# Sheet_SmartTerminal_2024-09-08.net
KiCad netlist of a schematic drawn in Altium Designer
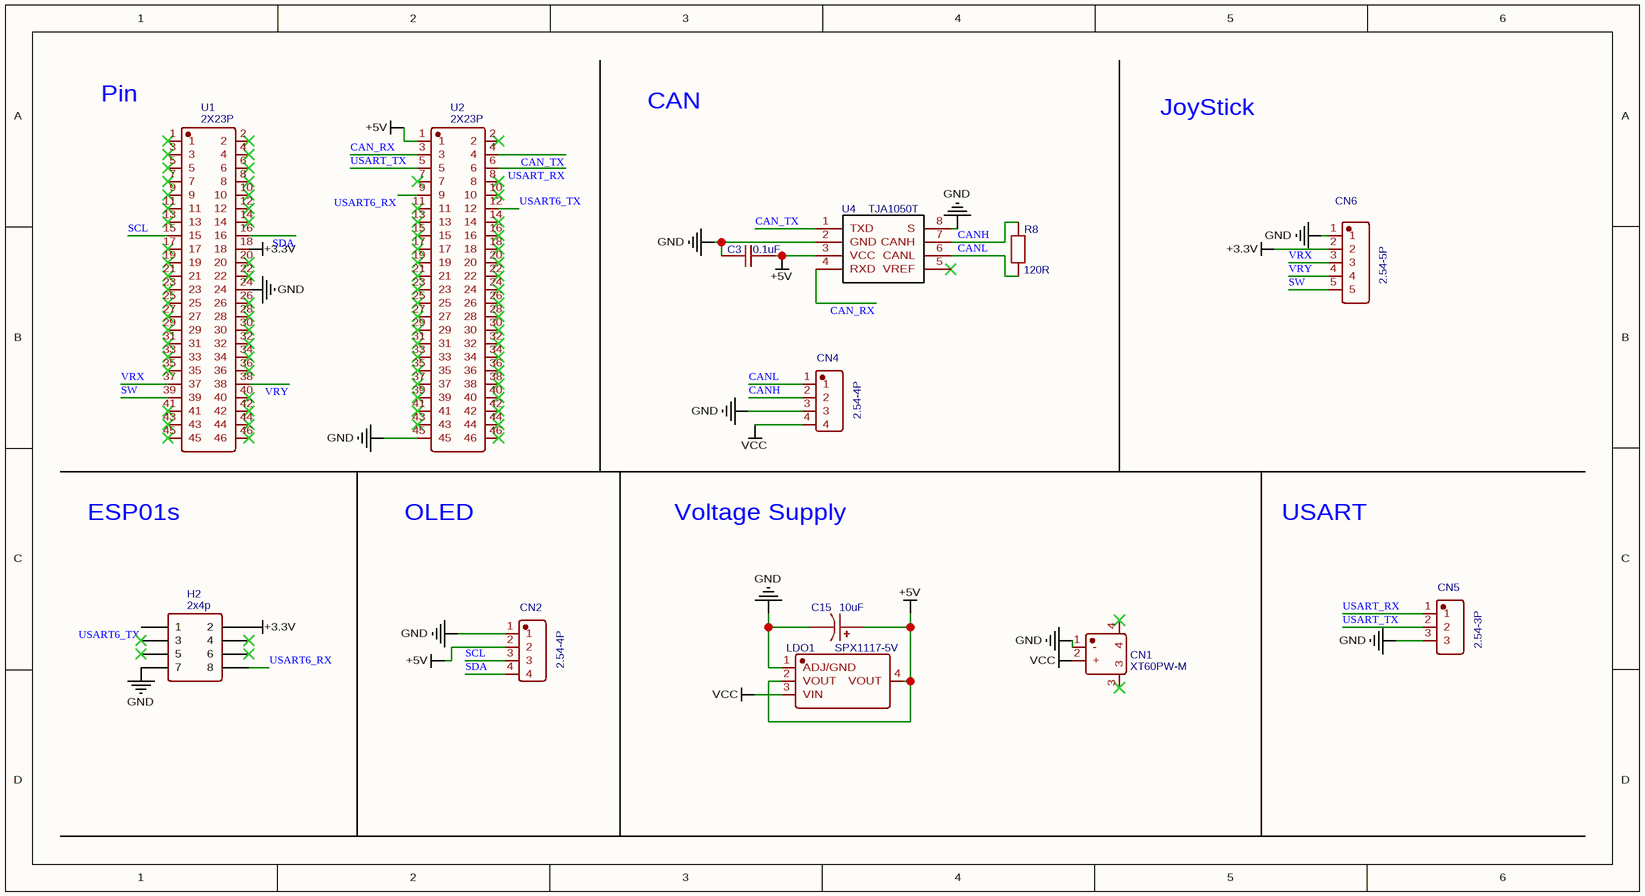
[diagram p0: Sheet_SmartTerminal_2024-09-08.schdoc]

(export (version "E")
  (design (tool "Eeschema 10.0.6"))
  (components
    (comp (ref "C3")
      (value "0.1uF")
      (fields (field (name "CONTRIBUTOR") "LCEDA_Lib"))
      (libsource (lib "altium-import") (part "root_0_0.1uF_"))
    )
    (comp (ref "C15")
      (value "10uF")
      (fields (field (name "CONTRIBUTOR") "LCEDA_Lib"))
      (libsource (lib "altium-import") (part "root_2_10uF_"))
    )
    (comp (ref "CN1")
      (value "XT60PW-M")
      (fields (field (name "MANUFACTURER") "AMASS(艾迈斯)") (field (name "CONTRIBUTOR") "LCSC"))
      (libsource (lib "altium-import") (part "root_0_XT60PW-M_"))
    )
    (comp (ref "CN2")
      (value "2.54-4P")
      (fields
        (field (name "MANUFACTURER") "HCTL(华灿天禄)")
        (field (name "MANUFACTURER PART") "XH-4AW")
        (field (name "CONTRIBUTOR") "LCSC")
      )
      (libsource (lib "altium-import") (part "root_0_2.54-4P_"))
    )
    (comp (ref "CN4")
      (value "2.54-4P")
      (fields
        (field (name "MANUFACTURER") "HCTL(华灿天禄)")
        (field (name "MANUFACTURER PART") "XH-4AW")
        (field (name "CONTRIBUTOR") "LCSC")
      )
      (libsource (lib "altium-import") (part "root_0_2.54-4P_"))
    )
    (comp (ref "CN5")
      (value "2.54-3P")
      (fields
        (field (name "MANUFACTURER") "HCTL(华灿天禄)")
        (field (name "MANUFACTURER PART") "XH-3AW")
        (field (name "CONTRIBUTOR") "LCSC")
      )
      (libsource (lib "altium-import") (part "root_0_2.54-3P_"))
    )
    (comp (ref "CN6")
      (value "2.54-5P")
      (fields
        (field (name "MANUFACTURER") "HCTL(华灿天禄)")
        (field (name "MANUFACTURER PART") "XH-5AW")
        (field (name "CONTRIBUTOR") "LCSC")
      )
      (libsource (lib "altium-import") (part "root_0_2.54-5P_"))
    )
    (comp (ref "H2")
      (value "2x4p")
      (fields
        (field (name "MANUFACTURER") "CONNFLY")
        (field (name "MANUFACTURER PART") "DS1023-2*4SF11")
        (field (name "CONTRIBUTOR") "LCSC")
      )
      (libsource (lib "altium-import") (part "root_0_2x4p_"))
    )
    (comp (ref "LDO1")
      (value "SPX1117-5V")
      (fields
        (field (name "BOM_MANUFACTURER PART") "SPX1117M3-L/TR")
        (field (name "BOM_SUPPLIER PART") "C67402")
      )
      (libsource (lib "altium-import") (part "root_0_SPX1117-5V_"))
    )
    (comp (ref "R8")
      (value "120R")
      (fields (field (name "CONTRIBUTOR") "LCEDA_Lib"))
      (libsource (lib "altium-import") (part "root_1_120R_"))
    )
    (comp (ref "U1")
      (value "2X23P")
      (fields
        (field (name "MANUFACTURER") "XKB Connection(中国星坤)")
        (field (name "MANUFACTURER PART") "X6522WV-2x23H-C60D30-E80")
        (field (name "CONTRIBUTOR") "lcsc")
      )
      (libsource (lib "altium-import") (part "root_0_2X23P_"))
    )
    (comp (ref "U2")
      (value "2X23P")
      (fields
        (field (name "MANUFACTURER") "XKB Connection(中国星坤)")
        (field (name "MANUFACTURER PART") "X6522WV-2x23H-C60D30-E80")
        (field (name "CONTRIBUTOR") "lcsc")
      )
      (libsource (lib "altium-import") (part "root_0_2X23P_"))
    )
    (comp (ref "U4")
      (value "TJA1050T")
      (fields
        (field (name "BOM_MANUFACTURER PART") "TJA1050T/CM,118")
        (field (name "BOM_SUPPLIER PART") "C6952")
      )
      (libsource (lib "altium-import") (part "root_0_TJA1050T_"))
    )
  )
  (nets
    (net (code "1") (name "+3.3V") (class "Default")
      (node (ref "CN6") (pin "2") (pinfunction "2_2") (pintype "passive"))
      (node (ref "H2") (pin "2") (pinfunction "2_2") (pintype "passive"))
      (node (ref "U1") (pin "18") (pinfunction "18_18") (pintype "passive"))
    )
    (net (code "2") (name "+5V") (class "Default")
      (node (ref "C15") (pin "1") (pinfunction "1_1") (pintype "passive"))
      (node (ref "C3") (pin "2") (pinfunction "2_2") (pintype "passive"))
      (node (ref "CN2") (pin "2") (pinfunction "2_2") (pintype "passive"))
      (node (ref "LDO1") (pin "2") (pinfunction "VOUT_2") (pintype "passive"))
      (node (ref "LDO1") (pin "4") (pinfunction "VOUT_4") (pintype "passive"))
      (node (ref "U2") (pin "1") (pinfunction "1_1") (pintype "passive"))
      (node (ref "U4") (pin "3") (pinfunction "VCC_3") (pintype "passive"))
    )
    (net (code "3") (name "/CANH") (class "Default")
      (node (ref "CN4") (pin "2") (pinfunction "2_2") (pintype "passive"))
      (node (ref "R8") (pin "2") (pinfunction "2_2") (pintype "passive"))
      (node (ref "U4") (pin "7") (pinfunction "CANH_7") (pintype "passive"))
    )
    (net (code "4") (name "/CANL") (class "Default")
      (node (ref "CN4") (pin "1") (pinfunction "1_1") (pintype "passive"))
      (node (ref "R8") (pin "1") (pinfunction "1_1") (pintype "passive"))
      (node (ref "U4") (pin "6") (pinfunction "CANL_6") (pintype "passive"))
    )
    (net (code "5") (name "/CAN_RX") (class "Default")
      (node (ref "U2") (pin "3") (pinfunction "3_3") (pintype "passive"))
      (node (ref "U4") (pin "4") (pinfunction "RXD_4") (pintype "passive"))
    )
    (net (code "6") (name "/CAN_TX") (class "Default")
      (node (ref "U2") (pin "4") (pinfunction "4_4") (pintype "passive"))
      (node (ref "U4") (pin "1") (pinfunction "TXD_1") (pintype "passive"))
    )
    (net (code "7") (name "/SCL") (class "Default")
      (node (ref "CN2") (pin "3") (pinfunction "3_3") (pintype "passive"))
      (node (ref "U1") (pin "15") (pinfunction "15_15") (pintype "passive"))
    )
    (net (code "8") (name "/SDA") (class "Default")
      (node (ref "CN2") (pin "4") (pinfunction "4_4") (pintype "passive"))
      (node (ref "U1") (pin "16") (pinfunction "16_16") (pintype "passive"))
    )
    (net (code "9") (name "/SW") (class "Default")
      (node (ref "CN6") (pin "5") (pinfunction "5_5") (pintype "passive"))
      (node (ref "U1") (pin "39") (pinfunction "39_39") (pintype "passive"))
    )
    (net (code "10") (name "/USART6_RX") (class "Default")
      (node (ref "H2") (pin "8") (pinfunction "8_8") (pintype "passive"))
      (node (ref "U2") (pin "9") (pinfunction "9_9") (pintype "passive"))
    )
    (net (code "11") (name "/USART6_TX") (class "Default")
      (node (ref "H2") (pin "1") (pinfunction "1_1") (pintype "passive"))
      (node (ref "U2") (pin "12") (pinfunction "12_12") (pintype "passive"))
    )
    (net (code "12") (name "/USART_RX") (class "Default")
      (node (ref "CN5") (pin "1") (pinfunction "1_1") (pintype "passive"))
      (node (ref "U2") (pin "6") (pinfunction "6_6") (pintype "passive"))
    )
    (net (code "13") (name "/USART_TX") (class "Default")
      (node (ref "CN5") (pin "2") (pinfunction "2_2") (pintype "passive"))
      (node (ref "U2") (pin "5") (pinfunction "5_5") (pintype "passive"))
    )
    (net (code "14") (name "/VRX") (class "Default")
      (node (ref "CN6") (pin "3") (pinfunction "3_3") (pintype "passive"))
      (node (ref "U1") (pin "37") (pinfunction "37_37") (pintype "passive"))
    )
    (net (code "15") (name "/VRY") (class "Default")
      (node (ref "CN6") (pin "4") (pinfunction "4_4") (pintype "passive"))
      (node (ref "U1") (pin "38") (pinfunction "38_38") (pintype "passive"))
    )
    (net (code "16") (name "GND") (class "Default")
      (node (ref "C15") (pin "2") (pinfunction "2_2") (pintype "passive"))
      (node (ref "C3") (pin "1") (pinfunction "1_1") (pintype "passive"))
      (node (ref "CN1") (pin "1") (pinfunction "-_1") (pintype "passive"))
      (node (ref "CN2") (pin "1") (pinfunction "1_1") (pintype "passive"))
      (node (ref "CN4") (pin "3") (pinfunction "3_3") (pintype "passive"))
      (node (ref "CN5") (pin "3") (pinfunction "3_3") (pintype "passive"))
      (node (ref "CN6") (pin "1") (pinfunction "1_1") (pintype "passive"))
      (node (ref "H2") (pin "7") (pinfunction "7_7") (pintype "passive"))
      (node (ref "LDO1") (pin "1") (pinfunction "ADJ/GND_1") (pintype "passive"))
      (node (ref "U1") (pin "24") (pinfunction "24_24") (pintype "passive"))
      (node (ref "U2") (pin "45") (pinfunction "45_45") (pintype "passive"))
      (node (ref "U4") (pin "2") (pinfunction "GND_2") (pintype "passive"))
      (node (ref "U4") (pin "8") (pinfunction "S_8") (pintype "passive"))
    )
    (net (code "17") (name "VCC") (class "Default")
      (node (ref "CN1") (pin "2") (pinfunction "+_2") (pintype "passive"))
      (node (ref "CN4") (pin "4") (pinfunction "4_4") (pintype "passive"))
      (node (ref "LDO1") (pin "3") (pinfunction "VIN_3") (pintype "passive"))
    )
    (net (code "18") (name "unconnected-(CN1-Pad3)") (class "Default")
      (node (ref "CN1") (pin "3") (pinfunction "3_3") (pintype "passive+no_connect"))
    )
    (net (code "19") (name "unconnected-(CN1-Pad4)") (class "Default")
      (node (ref "CN1") (pin "4") (pinfunction "4_4") (pintype "passive+no_connect"))
    )
    (net (code "20") (name "unconnected-(H2-Pad3)") (class "Default")
      (node (ref "H2") (pin "3") (pinfunction "3_3") (pintype "passive+no_connect"))
    )
    (net (code "21") (name "unconnected-(H2-Pad4)") (class "Default")
      (node (ref "H2") (pin "4") (pinfunction "4_4") (pintype "passive+no_connect"))
    )
    (net (code "22") (name "unconnected-(H2-Pad5)") (class "Default")
      (node (ref "H2") (pin "5") (pinfunction "5_5") (pintype "passive+no_connect"))
    )
    (net (code "23") (name "unconnected-(H2-Pad6)") (class "Default")
      (node (ref "H2") (pin "6") (pinfunction "6_6") (pintype "passive+no_connect"))
    )
    (net (code "24") (name "unconnected-(U1-Pad1)") (class "Default")
      (node (ref "U1") (pin "1") (pinfunction "1_1") (pintype "passive+no_connect"))
    )
    (net (code "25") (name "unconnected-(U1-Pad2)") (class "Default")
      (node (ref "U1") (pin "2") (pinfunction "2_2") (pintype "passive+no_connect"))
    )
    (net (code "26") (name "unconnected-(U1-Pad3)") (class "Default")
      (node (ref "U1") (pin "3") (pinfunction "3_3") (pintype "passive+no_connect"))
    )
    (net (code "27") (name "unconnected-(U1-Pad4)") (class "Default")
      (node (ref "U1") (pin "4") (pinfunction "4_4") (pintype "passive+no_connect"))
    )
    (net (code "28") (name "unconnected-(U1-Pad5)") (class "Default")
      (node (ref "U1") (pin "5") (pinfunction "5_5") (pintype "passive+no_connect"))
    )
    (net (code "29") (name "unconnected-(U1-Pad6)") (class "Default")
      (node (ref "U1") (pin "6") (pinfunction "6_6") (pintype "passive+no_connect"))
    )
    (net (code "30") (name "unconnected-(U1-Pad7)") (class "Default")
      (node (ref "U1") (pin "7") (pinfunction "7_7") (pintype "passive+no_connect"))
    )
    (net (code "31") (name "unconnected-(U1-Pad8)") (class "Default")
      (node (ref "U1") (pin "8") (pinfunction "8_8") (pintype "passive+no_connect"))
    )
    (net (code "32") (name "unconnected-(U1-Pad9)") (class "Default")
      (node (ref "U1") (pin "9") (pinfunction "9_9") (pintype "passive+no_connect"))
    )
    (net (code "33") (name "unconnected-(U1-Pad10)") (class "Default")
      (node (ref "U1") (pin "10") (pinfunction "10_10") (pintype "passive+no_connect"))
    )
    (net (code "34") (name "unconnected-(U1-Pad11)") (class "Default")
      (node (ref "U1") (pin "11") (pinfunction "11_11") (pintype "passive+no_connect"))
    )
    (net (code "35") (name "unconnected-(U1-Pad12)") (class "Default")
      (node (ref "U1") (pin "12") (pinfunction "12_12") (pintype "passive+no_connect"))
    )
    (net (code "36") (name "unconnected-(U1-Pad13)") (class "Default")
      (node (ref "U1") (pin "13") (pinfunction "13_13") (pintype "passive+no_connect"))
    )
    (net (code "37") (name "unconnected-(U1-Pad14)") (class "Default")
      (node (ref "U1") (pin "14") (pinfunction "14_14") (pintype "passive+no_connect"))
    )
    (net (code "38") (name "unconnected-(U1-Pad17)") (class "Default")
      (node (ref "U1") (pin "17") (pinfunction "17_17") (pintype "passive+no_connect"))
    )
    (net (code "39") (name "unconnected-(U1-Pad19)") (class "Default")
      (node (ref "U1") (pin "19") (pinfunction "19_19") (pintype "passive+no_connect"))
    )
    (net (code "40") (name "unconnected-(U1-Pad20)") (class "Default")
      (node (ref "U1") (pin "20") (pinfunction "20_20") (pintype "passive+no_connect"))
    )
    (net (code "41") (name "unconnected-(U1-Pad21)") (class "Default")
      (node (ref "U1") (pin "21") (pinfunction "21_21") (pintype "passive+no_connect"))
    )
    (net (code "42") (name "unconnected-(U1-Pad22)") (class "Default")
      (node (ref "U1") (pin "22") (pinfunction "22_22") (pintype "passive+no_connect"))
    )
    (net (code "43") (name "unconnected-(U1-Pad23)") (class "Default")
      (node (ref "U1") (pin "23") (pinfunction "23_23") (pintype "passive+no_connect"))
    )
    (net (code "44") (name "unconnected-(U1-Pad25)") (class "Default")
      (node (ref "U1") (pin "25") (pinfunction "25_25") (pintype "passive+no_connect"))
    )
    (net (code "45") (name "unconnected-(U1-Pad26)") (class "Default")
      (node (ref "U1") (pin "26") (pinfunction "26_26") (pintype "passive+no_connect"))
    )
    (net (code "46") (name "unconnected-(U1-Pad27)") (class "Default")
      (node (ref "U1") (pin "27") (pinfunction "27_27") (pintype "passive+no_connect"))
    )
    (net (code "47") (name "unconnected-(U1-Pad28)") (class "Default")
      (node (ref "U1") (pin "28") (pinfunction "28_28") (pintype "passive+no_connect"))
    )
    (net (code "48") (name "unconnected-(U1-Pad29)") (class "Default")
      (node (ref "U1") (pin "29") (pinfunction "29_29") (pintype "passive+no_connect"))
    )
    (net (code "49") (name "unconnected-(U1-Pad30)") (class "Default")
      (node (ref "U1") (pin "30") (pinfunction "30_30") (pintype "passive+no_connect"))
    )
    (net (code "50") (name "unconnected-(U1-Pad31)") (class "Default")
      (node (ref "U1") (pin "31") (pinfunction "31_31") (pintype "passive+no_connect"))
    )
    (net (code "51") (name "unconnected-(U1-Pad32)") (class "Default")
      (node (ref "U1") (pin "32") (pinfunction "32_32") (pintype "passive+no_connect"))
    )
    (net (code "52") (name "unconnected-(U1-Pad33)") (class "Default")
      (node (ref "U1") (pin "33") (pinfunction "33_33") (pintype "passive+no_connect"))
    )
    (net (code "53") (name "unconnected-(U1-Pad34)") (class "Default")
      (node (ref "U1") (pin "34") (pinfunction "34_34") (pintype "passive+no_connect"))
    )
    (net (code "54") (name "unconnected-(U1-Pad35)") (class "Default")
      (node (ref "U1") (pin "35") (pinfunction "35_35") (pintype "passive+no_connect"))
    )
    (net (code "55") (name "unconnected-(U1-Pad36)") (class "Default")
      (node (ref "U1") (pin "36") (pinfunction "36_36") (pintype "passive+no_connect"))
    )
    (net (code "56") (name "unconnected-(U1-Pad40)") (class "Default")
      (node (ref "U1") (pin "40") (pinfunction "40_40") (pintype "passive+no_connect"))
    )
    (net (code "57") (name "unconnected-(U1-Pad41)") (class "Default")
      (node (ref "U1") (pin "41") (pinfunction "41_41") (pintype "passive+no_connect"))
    )
    (net (code "58") (name "unconnected-(U1-Pad42)") (class "Default")
      (node (ref "U1") (pin "42") (pinfunction "42_42") (pintype "passive+no_connect"))
    )
    (net (code "59") (name "unconnected-(U1-Pad43)") (class "Default")
      (node (ref "U1") (pin "43") (pinfunction "43_43") (pintype "passive+no_connect"))
    )
    (net (code "60") (name "unconnected-(U1-Pad44)") (class "Default")
      (node (ref "U1") (pin "44") (pinfunction "44_44") (pintype "passive+no_connect"))
    )
    (net (code "61") (name "unconnected-(U1-Pad45)") (class "Default")
      (node (ref "U1") (pin "45") (pinfunction "45_45") (pintype "passive+no_connect"))
    )
    (net (code "62") (name "unconnected-(U1-Pad46)") (class "Default")
      (node (ref "U1") (pin "46") (pinfunction "46_46") (pintype "passive+no_connect"))
    )
    (net (code "63") (name "unconnected-(U2-Pad2)") (class "Default")
      (node (ref "U2") (pin "2") (pinfunction "2_2") (pintype "passive+no_connect"))
    )
    (net (code "64") (name "unconnected-(U2-Pad7)") (class "Default")
      (node (ref "U2") (pin "7") (pinfunction "7_7") (pintype "passive+no_connect"))
    )
    (net (code "65") (name "unconnected-(U2-Pad8)") (class "Default")
      (node (ref "U2") (pin "8") (pinfunction "8_8") (pintype "passive+no_connect"))
    )
    (net (code "66") (name "unconnected-(U2-Pad10)") (class "Default")
      (node (ref "U2") (pin "10") (pinfunction "10_10") (pintype "passive+no_connect"))
    )
    (net (code "67") (name "unconnected-(U2-Pad11)") (class "Default")
      (node (ref "U2") (pin "11") (pinfunction "11_11") (pintype "passive+no_connect"))
    )
    (net (code "68") (name "unconnected-(U2-Pad13)") (class "Default")
      (node (ref "U2") (pin "13") (pinfunction "13_13") (pintype "passive+no_connect"))
    )
    (net (code "69") (name "unconnected-(U2-Pad14)") (class "Default")
      (node (ref "U2") (pin "14") (pinfunction "14_14") (pintype "passive+no_connect"))
    )
    (net (code "70") (name "unconnected-(U2-Pad15)") (class "Default")
      (node (ref "U2") (pin "15") (pinfunction "15_15") (pintype "passive+no_connect"))
    )
    (net (code "71") (name "unconnected-(U2-Pad16)") (class "Default")
      (node (ref "U2") (pin "16") (pinfunction "16_16") (pintype "passive+no_connect"))
    )
    (net (code "72") (name "unconnected-(U2-Pad17)") (class "Default")
      (node (ref "U2") (pin "17") (pinfunction "17_17") (pintype "passive+no_connect"))
    )
    (net (code "73") (name "unconnected-(U2-Pad18)") (class "Default")
      (node (ref "U2") (pin "18") (pinfunction "18_18") (pintype "passive+no_connect"))
    )
    (net (code "74") (name "unconnected-(U2-Pad19)") (class "Default")
      (node (ref "U2") (pin "19") (pinfunction "19_19") (pintype "passive+no_connect"))
    )
    (net (code "75") (name "unconnected-(U2-Pad20)") (class "Default")
      (node (ref "U2") (pin "20") (pinfunction "20_20") (pintype "passive+no_connect"))
    )
    (net (code "76") (name "unconnected-(U2-Pad21)") (class "Default")
      (node (ref "U2") (pin "21") (pinfunction "21_21") (pintype "passive+no_connect"))
    )
    (net (code "77") (name "unconnected-(U2-Pad22)") (class "Default")
      (node (ref "U2") (pin "22") (pinfunction "22_22") (pintype "passive+no_connect"))
    )
    (net (code "78") (name "unconnected-(U2-Pad23)") (class "Default")
      (node (ref "U2") (pin "23") (pinfunction "23_23") (pintype "passive+no_connect"))
    )
    (net (code "79") (name "unconnected-(U2-Pad24)") (class "Default")
      (node (ref "U2") (pin "24") (pinfunction "24_24") (pintype "passive+no_connect"))
    )
    (net (code "80") (name "unconnected-(U2-Pad25)") (class "Default")
      (node (ref "U2") (pin "25") (pinfunction "25_25") (pintype "passive+no_connect"))
    )
    (net (code "81") (name "unconnected-(U2-Pad26)") (class "Default")
      (node (ref "U2") (pin "26") (pinfunction "26_26") (pintype "passive+no_connect"))
    )
    (net (code "82") (name "unconnected-(U2-Pad27)") (class "Default")
      (node (ref "U2") (pin "27") (pinfunction "27_27") (pintype "passive+no_connect"))
    )
    (net (code "83") (name "unconnected-(U2-Pad28)") (class "Default")
      (node (ref "U2") (pin "28") (pinfunction "28_28") (pintype "passive+no_connect"))
    )
    (net (code "84") (name "unconnected-(U2-Pad29)") (class "Default")
      (node (ref "U2") (pin "29") (pinfunction "29_29") (pintype "passive+no_connect"))
    )
    (net (code "85") (name "unconnected-(U2-Pad30)") (class "Default")
      (node (ref "U2") (pin "30") (pinfunction "30_30") (pintype "passive+no_connect"))
    )
    (net (code "86") (name "unconnected-(U2-Pad31)") (class "Default")
      (node (ref "U2") (pin "31") (pinfunction "31_31") (pintype "passive+no_connect"))
    )
    (net (code "87") (name "unconnected-(U2-Pad32)") (class "Default")
      (node (ref "U2") (pin "32") (pinfunction "32_32") (pintype "passive+no_connect"))
    )
    (net (code "88") (name "unconnected-(U2-Pad33)") (class "Default")
      (node (ref "U2") (pin "33") (pinfunction "33_33") (pintype "passive+no_connect"))
    )
    (net (code "89") (name "unconnected-(U2-Pad34)") (class "Default")
      (node (ref "U2") (pin "34") (pinfunction "34_34") (pintype "passive+no_connect"))
    )
    (net (code "90") (name "unconnected-(U2-Pad35)") (class "Default")
      (node (ref "U2") (pin "35") (pinfunction "35_35") (pintype "passive+no_connect"))
    )
    (net (code "91") (name "unconnected-(U2-Pad36)") (class "Default")
      (node (ref "U2") (pin "36") (pinfunction "36_36") (pintype "passive+no_connect"))
    )
    (net (code "92") (name "unconnected-(U2-Pad37)") (class "Default")
      (node (ref "U2") (pin "37") (pinfunction "37_37") (pintype "passive+no_connect"))
    )
    (net (code "93") (name "unconnected-(U2-Pad38)") (class "Default")
      (node (ref "U2") (pin "38") (pinfunction "38_38") (pintype "passive+no_connect"))
    )
    (net (code "94") (name "unconnected-(U2-Pad39)") (class "Default")
      (node (ref "U2") (pin "39") (pinfunction "39_39") (pintype "passive+no_connect"))
    )
    (net (code "95") (name "unconnected-(U2-Pad40)") (class "Default")
      (node (ref "U2") (pin "40") (pinfunction "40_40") (pintype "passive+no_connect"))
    )
    (net (code "96") (name "unconnected-(U2-Pad41)") (class "Default")
      (node (ref "U2") (pin "41") (pinfunction "41_41") (pintype "passive+no_connect"))
    )
    (net (code "97") (name "unconnected-(U2-Pad42)") (class "Default")
      (node (ref "U2") (pin "42") (pinfunction "42_42") (pintype "passive+no_connect"))
    )
    (net (code "98") (name "unconnected-(U2-Pad43)") (class "Default")
      (node (ref "U2") (pin "43") (pinfunction "43_43") (pintype "passive+no_connect"))
    )
    (net (code "99") (name "unconnected-(U2-Pad44)") (class "Default")
      (node (ref "U2") (pin "44") (pinfunction "44_44") (pintype "passive+no_connect"))
    )
    (net (code "100") (name "unconnected-(U2-Pad46)") (class "Default")
      (node (ref "U2") (pin "46") (pinfunction "46_46") (pintype "passive+no_connect"))
    )
    (net (code "101") (name "unconnected-(U4-VREF-Pad5)") (class "Default")
      (node (ref "U4") (pin "5") (pinfunction "VREF_5") (pintype "passive+no_connect"))
    )
  )
)
